# BH1750.net
KiCad netlist of a schematic drawn in Altium Designer
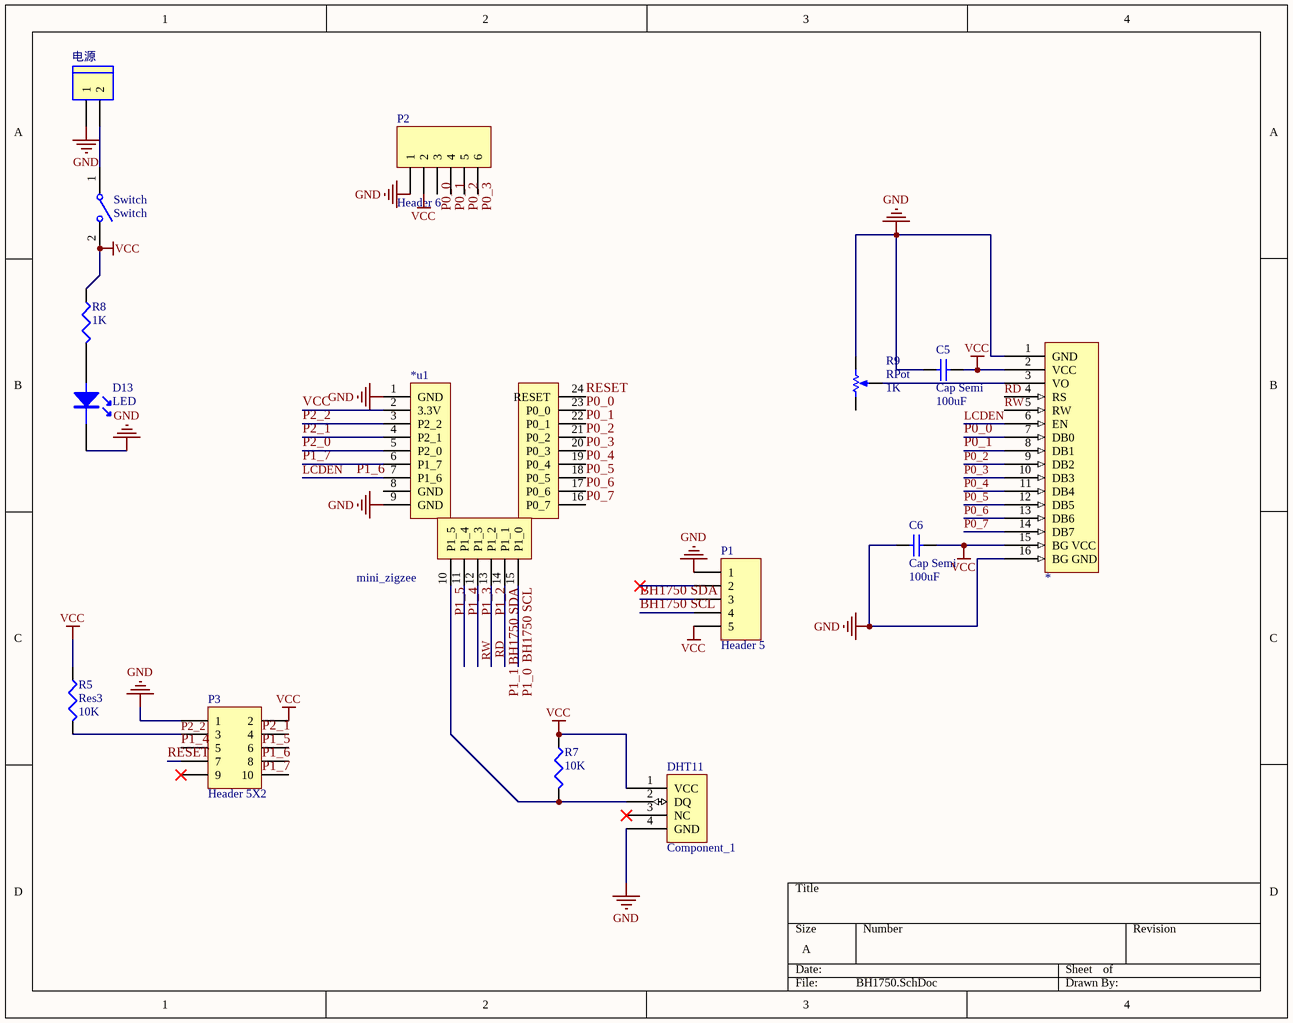
[diagram p0: BH1750.SchDoc]

(export (version "E")
  (design (tool "Eeschema 10.0.6"))
  (components
    (comp (ref "*")
      (value "Component_1")
      (footprint "HDR1X16")
      (libsource (lib "LCD1602") (part "Component_1"))
    )
    (comp (ref "*u1")
      (value "mini_zigzee")
      (footprint "mini_zigbee")
      (libsource (lib "*") (part "mini_zigzee"))
    )
    (comp (ref "C5")
      (value "Cap Semi")
      (footprint "C1206")
      (description "Capacitor (Semiconductor SIM Model)")
      (fields (field (name "ALTIUM_VALUE") "100uF") (field (name "PUBLISHER") "Altium Limited"))
      (libsource (lib "Miscellaneous Devices") (part "Cap Semi"))
    )
    (comp (ref "C6")
      (value "Cap Semi")
      (footprint "C1206")
      (description "Capacitor (Semiconductor SIM Model)")
      (fields (field (name "ALTIUM_VALUE") "100uF") (field (name "PUBLISHER") "Altium Limited"))
      (libsource (lib "Miscellaneous Devices") (part "Cap Semi"))
    )
    (comp (ref "D13") (value "LED") (footprint "LED") (libsource (lib "FS44B0_CORE") (part "LED_1")))
    (comp (ref "DHT11")
      (value "Component_1")
      (footprint "HDR1X4")
      (libsource (lib "DHT11") (part "Component_1"))
    )
    (comp (ref "P1")
      (value "Header 5")
      (footprint "HDR1X5")
      (description "Header, 5-Pin")
      (fields (field (name "PUBLISHER") "Altium Limited"))
      (libsource (lib "Miscellaneous Connectors") (part "Header 5"))
    )
    (comp (ref "P2")
      (value "Header 6")
      (footprint "HDR1X6")
      (description "Header, 6-Pin")
      (fields (field (name "PUBLISHER") "Altium Limited"))
      (libsource (lib "Miscellaneous Connectors") (part "Header 6"))
    )
    (comp (ref "P3")
      (value "Header 5X2")
      (footprint "HDR2X5")
      (description "Header, 5-Pin, Dual row")
      (fields (field (name "PUBLISHER") "Altium Limited"))
      (libsource (lib "Miscellaneous Connectors") (part "Header 5X2"))
    )
    (comp (ref "R5")
      (value "Res3")
      (footprint "J1-0603")
      (description "Resistor")
      (fields (field (name "ALTIUM_VALUE") "10K") (field (name "PUBLISHER") "Altium Limited"))
      (libsource (lib "Miscellaneous Devices") (part "Res3"))
    )
    (comp (ref "R7")
      (value "10K")
      (footprint "J1-0603")
      (description "Resistor")
      (fields (field (name "Comment") "Res3") (field (name "PUBLISHER") "Altium Limited"))
      (libsource (lib "Miscellaneous Devices") (part "Res3"))
    )
    (comp (ref "R8")
      (value "1K")
      (footprint "J1-0603")
      (description "Resistor")
      (fields (field (name "Comment") "Res3") (field (name "PUBLISHER") "Altium Limited"))
      (libsource (lib "Miscellaneous Devices") (part "Res3"))
    )
    (comp (ref "R9")
      (value "RPot")
      (footprint "TO-205AF")
      (description "Potentiometer")
      (fields (field (name "ALTIUM_VALUE") "1K") (field (name "PUBLISHER") "Altium Limited"))
      (libsource (lib "Miscellaneous Devices") (part "RPot"))
    )
    (comp (ref "Switch")
      (value "Switch")
      (footprint "Switch")
      (libsource (lib "my Integrated lib ") (part "Switch"))
    )
    (comp (ref "电源")
      (value "~")
      (footprint "HDR1X2")
      (description "Header, 2-Pin")
      (fields (field (name "MANUFACTURER") "Generic Components"))
      (libsource (lib "hecheng") (part "H-2"))
    )
  )
  (nets
    (net (code "1") (name "/BH1750 SCL") (class "Default")
      (node (ref "*u1") (pin "15") (pinfunction "P1_0_15") (pintype "passive"))
      (node (ref "P1") (pin "4") (pinfunction "4_4") (pintype "passive"))
    )
    (net (code "2") (name "/BH1750 SDA") (class "Default")
      (node (ref "*u1") (pin "14") (pinfunction "P1_1_14") (pintype "passive"))
      (node (ref "P1") (pin "3") (pinfunction "3_3") (pintype "passive"))
    )
    (net (code "3") (name "/LCDEN") (class "Default")
      (node (ref "*") (pin "6") (pinfunction "EN_6") (pintype "input"))
      (node (ref "*u1") (pin "7") (pinfunction "P1_6_7") (pintype "passive"))
    )
    (net (code "4") (name "/P0_0") (class "Default")
      (node (ref "*") (pin "7") (pinfunction "DB0_7") (pintype "input"))
      (node (ref "*u1") (pin "23") (pinfunction "P0_0_23") (pintype "passive"))
    )
    (net (code "5") (name "/P0_1") (class "Default")
      (node (ref "*") (pin "8") (pinfunction "DB1_8") (pintype "input"))
      (node (ref "*u1") (pin "22") (pinfunction "P0_1_22") (pintype "passive"))
    )
    (net (code "6") (name "/P0_2") (class "Default")
      (node (ref "*") (pin "9") (pinfunction "DB2_9") (pintype "input"))
      (node (ref "*u1") (pin "21") (pinfunction "P0_2_21") (pintype "passive"))
    )
    (net (code "7") (name "/P0_3") (class "Default")
      (node (ref "*") (pin "10") (pinfunction "DB3_10") (pintype "input"))
      (node (ref "*u1") (pin "20") (pinfunction "P0_3_20") (pintype "passive"))
    )
    (net (code "8") (name "/P0_4") (class "Default")
      (node (ref "*") (pin "11") (pinfunction "DB4_11") (pintype "input"))
      (node (ref "*u1") (pin "19") (pinfunction "P0_4_19") (pintype "passive"))
    )
    (net (code "9") (name "/P0_5") (class "Default")
      (node (ref "*") (pin "12") (pinfunction "DB5_12") (pintype "input"))
      (node (ref "*u1") (pin "18") (pinfunction "P0_5_18") (pintype "passive"))
    )
    (net (code "10") (name "/P0_6") (class "Default")
      (node (ref "*") (pin "13") (pinfunction "DB6_13") (pintype "input"))
      (node (ref "*u1") (pin "17") (pinfunction "P0_6_17") (pintype "passive"))
    )
    (net (code "11") (name "/P0_7") (class "Default")
      (node (ref "*") (pin "14") (pinfunction "DB7_14") (pintype "input"))
      (node (ref "*u1") (pin "16") (pinfunction "P0_7_16") (pintype "passive"))
    )
    (net (code "12") (name "/P1_2") (class "Default")
      (node (ref "*") (pin "4") (pinfunction "RS_4") (pintype "input"))
      (node (ref "*u1") (pin "13") (pinfunction "P1_2_13") (pintype "passive"))
    )
    (net (code "13") (name "/P1_3") (class "Default")
      (node (ref "*") (pin "5") (pinfunction "RW_5") (pintype "input"))
      (node (ref "*u1") (pin "12") (pinfunction "P1_3_12") (pintype "passive"))
    )
    (net (code "14") (name "/P1_4") (class "Default")
      (node (ref "*u1") (pin "11") (pinfunction "P1_4_11") (pintype "passive"))
      (node (ref "P3") (pin "5") (pinfunction "5_5") (pintype "passive"))
    )
    (net (code "15") (name "/P1_5") (class "Default")
      (node (ref "*u1") (pin "10") (pinfunction "P1_5_10") (pintype "passive"))
      (node (ref "DHT11") (pin "2") (pinfunction "DQ_2") (pintype "bidirectional"))
      (node (ref "R7") (pin "2") (pinfunction "2_2") (pintype "passive"))
    )
    (net (code "16") (name "/P1_7") (class "Default")
      (node (ref "*u1") (pin "6") (pinfunction "P1_7_6") (pintype "passive"))
    )
    (net (code "17") (name "/P2_0") (class "Default")
      (node (ref "*u1") (pin "5") (pinfunction "P2_0_5") (pintype "passive"))
    )
    (net (code "18") (name "/P2_1") (class "Default")
      (node (ref "*u1") (pin "4") (pinfunction "P2_1_4") (pintype "passive"))
    )
    (net (code "19") (name "/P2_2") (class "Default")
      (node (ref "*u1") (pin "3") (pinfunction "P2_2_3") (pintype "passive"))
      (node (ref "P3") (pin "3") (pinfunction "3_3") (pintype "passive"))
      (node (ref "R5") (pin "2") (pinfunction "2_2") (pintype "passive"))
    )
    (net (code "20") (name "/RESET") (class "Default")
      (node (ref "*u1") (pin "24") (pinfunction "RESET_24") (pintype "passive"))
      (node (ref "P3") (pin "7") (pinfunction "7_7") (pintype "passive"))
    )
    (net (code "21") (name "GND") (class "Default")
      (node (ref "*") (pin "1") (pinfunction "GND_1") (pintype "power_in"))
      (node (ref "*") (pin "16") (pinfunction "BG_GND_16") (pintype "input"))
      (node (ref "*u1") (pin "1") (pinfunction "GND_1") (pintype "passive"))
      (node (ref "*u1") (pin "9") (pinfunction "GND_9") (pintype "passive"))
      (node (ref "C5") (pin "1") (pinfunction "1_1") (pintype "passive"))
      (node (ref "C6") (pin "1") (pinfunction "1_1") (pintype "passive"))
      (node (ref "D13") (pin "K") (pinfunction "2_K") (pintype "passive"))
      (node (ref "DHT11") (pin "4") (pinfunction "GND_4") (pintype "power_in"))
      (node (ref "P1") (pin "1") (pinfunction "1_1") (pintype "passive"))
      (node (ref "P2") (pin "1") (pinfunction "1_1") (pintype "passive"))
      (node (ref "P3") (pin "1") (pinfunction "1_1") (pintype "passive"))
      (node (ref "R9") (pin "2") (pinfunction "BOT_2") (pintype "passive"))
      (node (ref "电源") (pin "1") (pinfunction "1_1") (pintype "passive"))
    )
    (net (code "22") (name "Net-(*-VO)") (class "Default")
      (node (ref "*") (pin "3") (pinfunction "VO_3") (pintype "passive"))
      (node (ref "R9") (pin "3") (pinfunction "TAP_3") (pintype "passive"))
    )
    (net (code "23") (name "Net-(D13-1)") (class "Default")
      (node (ref "D13") (pin "A") (pinfunction "1_A") (pintype "passive"))
      (node (ref "R8") (pin "2") (pinfunction "2_2") (pintype "passive"))
    )
    (net (code "24") (name "Net-(Switch-COMMON)") (class "Default")
      (node (ref "Switch") (pin "1") (pinfunction "COMMON_1") (pintype "passive"))
      (node (ref "电源") (pin "2") (pinfunction "2_2") (pintype "passive"))
    )
    (net (code "25") (name "VCC") (class "Default")
      (node (ref "*") (pin "15") (pinfunction "BG_VCC_15") (pintype "input"))
      (node (ref "*") (pin "2") (pinfunction "VCC_2") (pintype "power_in"))
      (node (ref "*u1") (pin "2") (pinfunction "3.3V_2") (pintype "passive"))
      (node (ref "C5") (pin "2") (pinfunction "2_2") (pintype "passive"))
      (node (ref "C6") (pin "2") (pinfunction "2_2") (pintype "passive"))
      (node (ref "DHT11") (pin "1") (pinfunction "VCC_1") (pintype "power_in"))
      (node (ref "P1") (pin "5") (pinfunction "5_5") (pintype "passive"))
      (node (ref "P2") (pin "2") (pinfunction "2_2") (pintype "passive"))
      (node (ref "P3") (pin "2") (pinfunction "2_2") (pintype "passive"))
      (node (ref "R5") (pin "1") (pinfunction "1_1") (pintype "passive"))
      (node (ref "R7") (pin "1") (pinfunction "1_1") (pintype "passive"))
      (node (ref "R8") (pin "1") (pinfunction "1_1") (pintype "passive"))
      (node (ref "Switch") (pin "2") (pinfunction "NO_2") (pintype "passive"))
    )
    (net (code "26") (name "unconnected-(*u1-GND-Pad8)") (class "Default")
      (node (ref "*u1") (pin "8") (pinfunction "GND_8") (pintype "passive"))
    )
    (net (code "27") (name "unconnected-(DHT11-NC-Pad3)") (class "Default")
      (node (ref "DHT11") (pin "3") (pinfunction "NC_3") (pintype "passive+no_connect"))
    )
    (net (code "28") (name "unconnected-(P1-Pad2)") (class "Default")
      (node (ref "P1") (pin "2") (pinfunction "2_2") (pintype "passive+no_connect"))
    )
    (net (code "29") (name "unconnected-(P2-Pad3)") (class "Default")
      (node (ref "P2") (pin "3") (pinfunction "3_3") (pintype "passive"))
    )
    (net (code "30") (name "unconnected-(P2-Pad4)") (class "Default")
      (node (ref "P2") (pin "4") (pinfunction "4_4") (pintype "passive"))
    )
    (net (code "31") (name "unconnected-(P2-Pad5)") (class "Default")
      (node (ref "P2") (pin "5") (pinfunction "5_5") (pintype "passive"))
    )
    (net (code "32") (name "unconnected-(P2-Pad6)") (class "Default")
      (node (ref "P2") (pin "6") (pinfunction "6_6") (pintype "passive"))
    )
    (net (code "33") (name "unconnected-(P3-Pad4)") (class "Default")
      (node (ref "P3") (pin "4") (pinfunction "4_4") (pintype "passive"))
    )
    (net (code "34") (name "unconnected-(P3-Pad6)") (class "Default")
      (node (ref "P3") (pin "6") (pinfunction "6_6") (pintype "passive"))
    )
    (net (code "35") (name "unconnected-(P3-Pad8)") (class "Default")
      (node (ref "P3") (pin "8") (pinfunction "8_8") (pintype "passive"))
    )
    (net (code "36") (name "unconnected-(P3-Pad9)") (class "Default")
      (node (ref "P3") (pin "9") (pinfunction "9_9") (pintype "passive+no_connect"))
    )
    (net (code "37") (name "unconnected-(P3-Pad10)") (class "Default")
      (node (ref "P3") (pin "10") (pinfunction "10_10") (pintype "passive"))
    )
    (net (code "38") (name "unconnected-(R9-TOP-Pad1)") (class "Default")
      (node (ref "R9") (pin "1") (pinfunction "TOP_1") (pintype "passive"))
    )
  )
)
